# MiiChrono.net
KiCad netlist of a schematic drawn in EAGLE
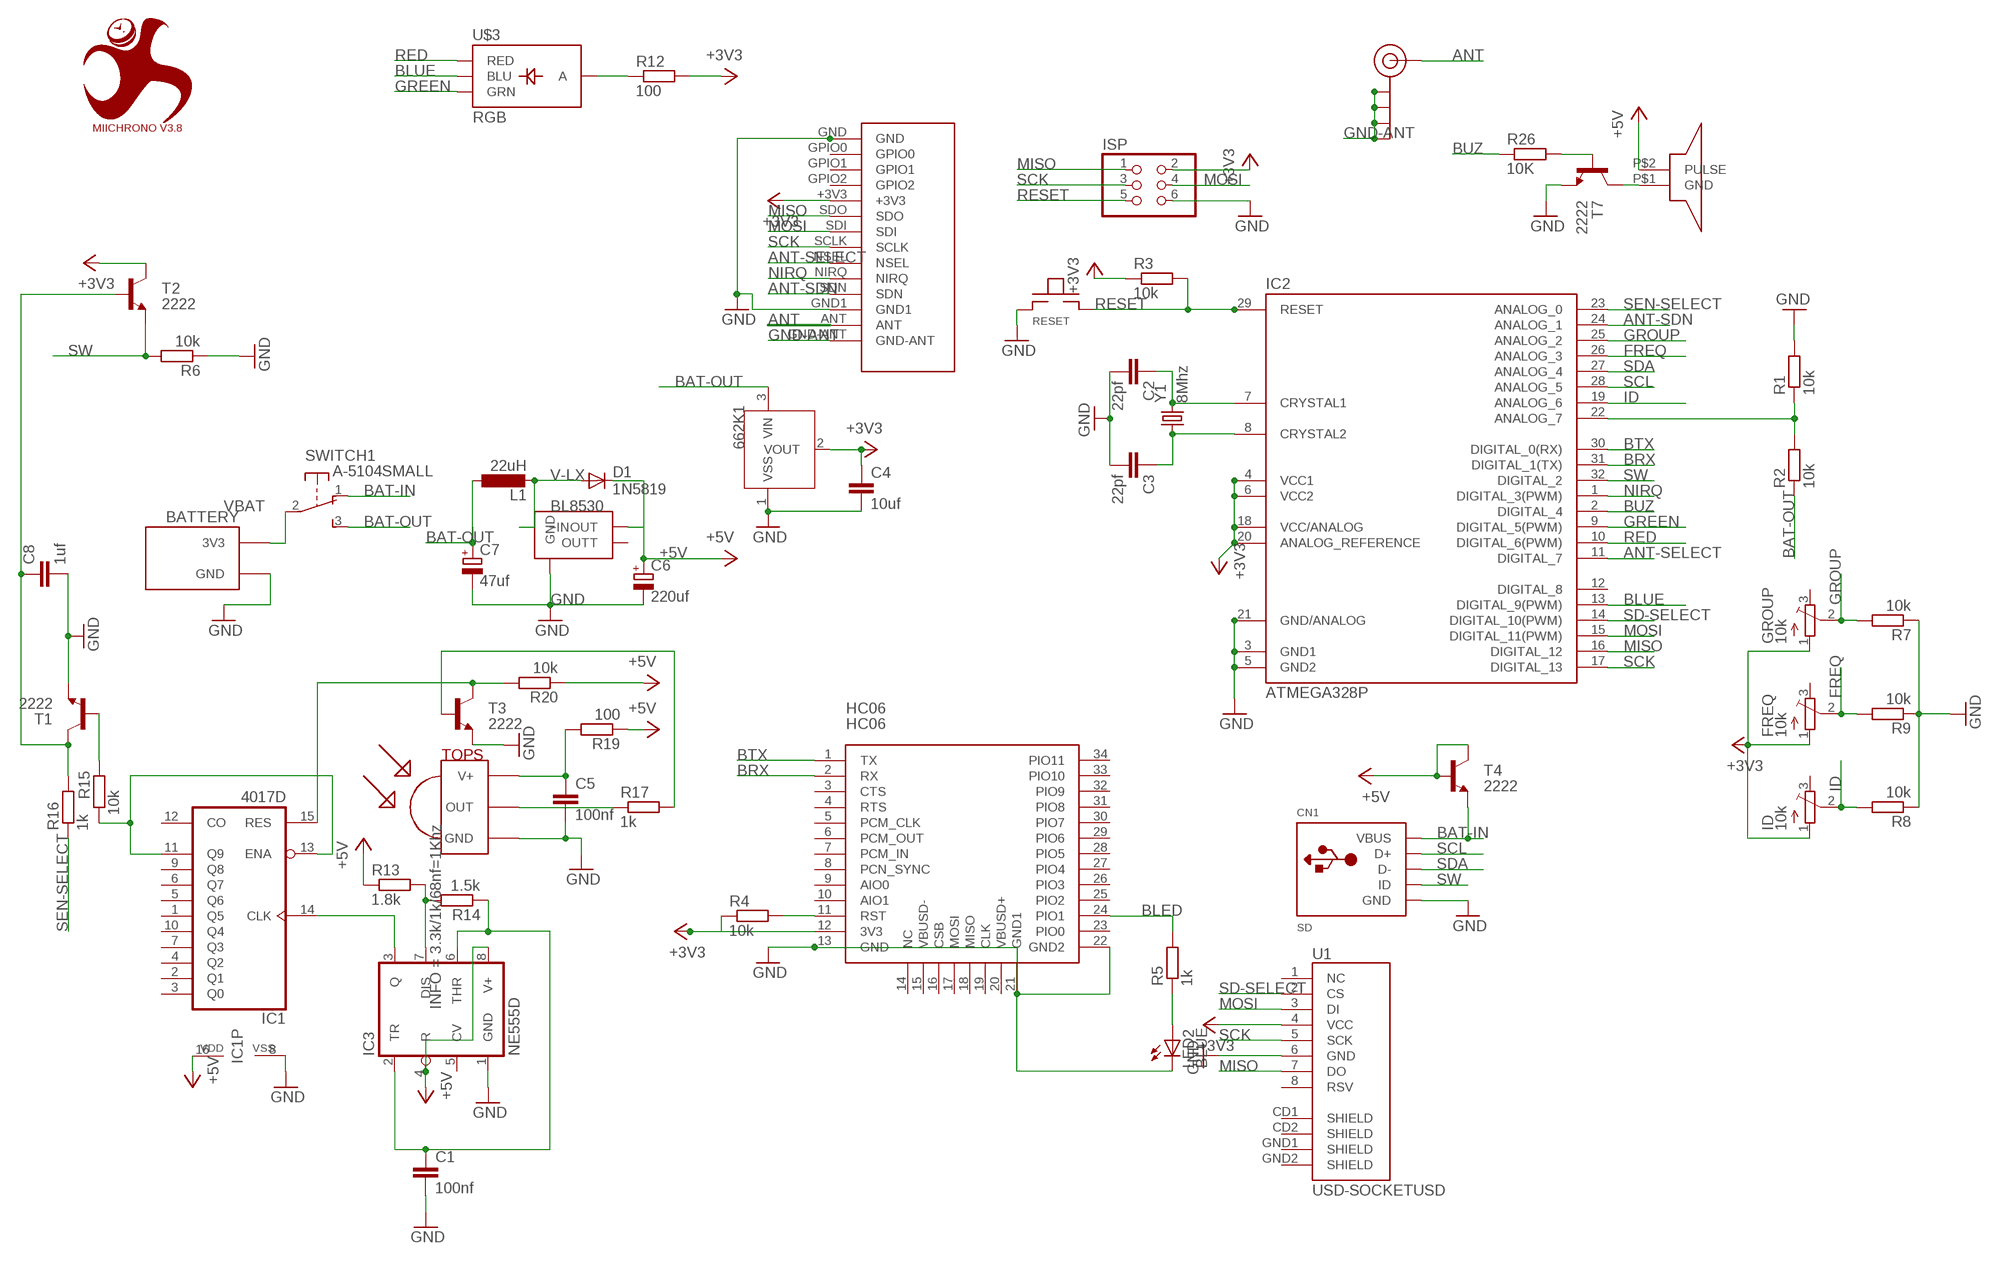
[diagram p0: schematic, sheet 1]

(export (version "E")
  (design (tool "Eeschema 10.0.6"))
  (components
    (comp (ref "662K1")
      (value "XC6206")
      (footprint "eagle-import:SOT23")
      (libsource (lib "eagle-import") (part "XC6206"))
    )
    (comp (ref "BATTERY")
      (value "GOPRO3BATTERY")
      (footprint "eagle-import:GOPRO3BATTERY")
      (libsource (lib "eagle-import") (part "GOPRO3BATTERY"))
    )
    (comp (ref "BL8530")
      (value "BL8530")
      (footprint "eagle-import:SOT89")
      (libsource (lib "eagle-import") (part "BL8530"))
    )
    (comp (ref "BUZZER")
      (value "BUZZER")
      (footprint "eagle-import:BUZZER")
      (libsource (lib "eagle-import") (part "BUZZER"))
    )
    (comp (ref "C1")
      (value "100nf")
      (footprint "eagle-import:C0805")
      (libsource (lib "eagle-import") (part "C-EUC0805"))
    )
    (comp (ref "C2")
      (value "22pf")
      (footprint "eagle-import:C0805")
      (libsource (lib "eagle-import") (part "C-EUC0805"))
    )
    (comp (ref "C3")
      (value "22pf")
      (footprint "eagle-import:C0805")
      (libsource (lib "eagle-import") (part "C-EUC0805"))
    )
    (comp (ref "C4")
      (value "10uf")
      (footprint "eagle-import:C0805")
      (libsource (lib "eagle-import") (part "C-EUC0805"))
    )
    (comp (ref "C5")
      (value "100nf")
      (footprint "eagle-import:C0805")
      (libsource (lib "eagle-import") (part "C-EUC0805"))
    )
    (comp (ref "C6")
      (value "220uf")
      (footprint "eagle-import:CT3528")
      (libsource (lib "eagle-import") (part "CPOL-EUCT3528"))
    )
    (comp (ref "C7")
      (value "47uf")
      (footprint "eagle-import:SMC_A")
      (libsource (lib "eagle-import") (part "CPOL-EUSMCA"))
    )
    (comp (ref "C8")
      (value "1uf")
      (footprint "eagle-import:C0805")
      (libsource (lib "eagle-import") (part "C-EUC0805"))
    )
    (comp (ref "CN1")
      (value "SD")
      (footprint "eagle-import:USB-MINIB")
      (libsource (lib "eagle-import") (part "USBMINIB"))
    )
    (comp (ref "D1")
      (value "1N5819")
      (footprint "eagle-import:DO214AC")
      (libsource (lib "eagle-import") (part "DIODE-DO214AC"))
    )
    (comp (ref "FREQ")
      (value "10k")
      (footprint "eagle-import:TC33X")
      (libsource (lib "eagle-import") (part "TRIMPOTTC33X"))
    )
    (comp (ref "GROUP")
      (value "10k")
      (footprint "eagle-import:TC33X")
      (libsource (lib "eagle-import") (part "TRIMPOTTC33X"))
    )
    (comp (ref "HC06")
      (value "HC06")
      (footprint "eagle-import:BLUETOOTH_SMD")
      (libsource (lib "eagle-import") (part "HC_05"))
    )
    (comp (ref "IC1")
      (value "4017D")
      (footprint "eagle-import:SO16")
      (libsource (lib "eagle-import") (part "4017D"))
    )
    (comp (ref "IC2")
      (value "ATMEGA328P")
      (footprint "eagle-import:TQFP32-08")
      (libsource (lib "eagle-import") (part "ATMEGA168-AU"))
    )
    (comp (ref "IC3")
      (value "NE555D")
      (footprint "eagle-import:SO08")
      (fields (field (name "INFO") "3.3k/1k/68nf=1Khz"))
      (libsource (lib "eagle-import") (part "555DNE"))
    )
    (comp (ref "ID")
      (value "10k")
      (footprint "eagle-import:TC33X")
      (libsource (lib "eagle-import") (part "TRIMPOTTC33X"))
    )
    (comp (ref "ISP")
      (value "PINHD-2X03_2.00")
      (footprint "eagle-import:2X03M")
      (libsource (lib "eagle-import") (part "PINHD-2X03_2.00"))
    )
    (comp (ref "J$1")
      (value "SMA_EDGE")
      (footprint "eagle-import:SMA-EDGE")
      (libsource (lib "eagle-import") (part "SMA_EDGE"))
    )
    (comp (ref "L1")
      (value "22uH")
      (footprint "eagle-import:L1812")
      (libsource (lib "eagle-import") (part "L-EUL1812"))
    )
    (comp (ref "LED2")
      (value "BLUE")
      (footprint "eagle-import:CHIP-LED0805")
      (libsource (lib "eagle-import") (part "LEDCHIP-LED0805"))
    )
    (comp (ref "R1")
      (value "10k")
      (footprint "eagle-import:R0805")
      (libsource (lib "eagle-import") (part "R-EU_R0805"))
    )
    (comp (ref "R2")
      (value "10k")
      (footprint "eagle-import:R0805")
      (libsource (lib "eagle-import") (part "R-EU_R0805"))
    )
    (comp (ref "R3")
      (value "10k")
      (footprint "eagle-import:R0805")
      (libsource (lib "eagle-import") (part "R-EU_R0805"))
    )
    (comp (ref "R4")
      (value "10k")
      (footprint "eagle-import:R0805")
      (libsource (lib "eagle-import") (part "R-EU_R0805"))
    )
    (comp (ref "R5")
      (value "1k")
      (footprint "eagle-import:R0805")
      (libsource (lib "eagle-import") (part "R-EU_R0805"))
    )
    (comp (ref "R6")
      (value "10k")
      (footprint "eagle-import:R0805")
      (libsource (lib "eagle-import") (part "R-EU_R0805"))
    )
    (comp (ref "R7")
      (value "10k")
      (footprint "eagle-import:R0805")
      (libsource (lib "eagle-import") (part "R-EU_R0805"))
    )
    (comp (ref "R8")
      (value "10k")
      (footprint "eagle-import:R0805")
      (libsource (lib "eagle-import") (part "R-EU_R0805"))
    )
    (comp (ref "R9")
      (value "10k")
      (footprint "eagle-import:R0805")
      (libsource (lib "eagle-import") (part "R-EU_R0805"))
    )
    (comp (ref "R12")
      (value "100")
      (footprint "eagle-import:R0805")
      (libsource (lib "eagle-import") (part "R-EU_R0805"))
    )
    (comp (ref "R13")
      (value "1.8k")
      (footprint "eagle-import:R0805")
      (libsource (lib "eagle-import") (part "R-EU_R0805"))
    )
    (comp (ref "R14")
      (value "1.5k")
      (footprint "eagle-import:R0805")
      (libsource (lib "eagle-import") (part "R-EU_R0805"))
    )
    (comp (ref "R15")
      (value "10k")
      (footprint "eagle-import:R0805")
      (libsource (lib "eagle-import") (part "R-EU_R0805"))
    )
    (comp (ref "R16")
      (value "1k")
      (footprint "eagle-import:R0805")
      (libsource (lib "eagle-import") (part "R-EU_R0805"))
    )
    (comp (ref "R17")
      (value "1k")
      (footprint "eagle-import:R0805")
      (libsource (lib "eagle-import") (part "R-EU_R0805"))
    )
    (comp (ref "R19")
      (value "100")
      (footprint "eagle-import:R0805")
      (libsource (lib "eagle-import") (part "R-EU_R0805"))
    )
    (comp (ref "R20")
      (value "10k")
      (footprint "eagle-import:R0805")
      (libsource (lib "eagle-import") (part "R-EU_R0805"))
    )
    (comp (ref "R26")
      (value "10K")
      (footprint "eagle-import:R0805")
      (libsource (lib "eagle-import") (part "R-EU_R0805"))
    )
    (comp (ref "RESET")
      (value "TACT")
      (footprint "eagle-import:TACT-TS-1289")
      (libsource (lib "eagle-import") (part "TACT"))
    )
    (comp (ref "SWITCH")
      (value "A-5104SMALL")
      (footprint "eagle-import:A-5104-SMALL")
      (libsource (lib "eagle-import") (part "A-5104SMALL"))
    )
    (comp (ref "T1")
      (value "2222")
      (footprint "eagle-import:SOT23")
      (libsource (lib "eagle-import") (part "TRANSISTOR_NPNSOT23"))
    )
    (comp (ref "T2")
      (value "2222")
      (footprint "eagle-import:SOT23")
      (libsource (lib "eagle-import") (part "TRANSISTOR_NPNSOT23"))
    )
    (comp (ref "T3")
      (value "2222")
      (footprint "eagle-import:SOT23")
      (libsource (lib "eagle-import") (part "TRANSISTOR_NPNSOT23"))
    )
    (comp (ref "T4")
      (value "2222")
      (footprint "eagle-import:SOT23")
      (libsource (lib "eagle-import") (part "TRANSISTOR_NPNSOT23"))
    )
    (comp (ref "T7")
      (value "2222")
      (footprint "eagle-import:SOT23")
      (libsource (lib "eagle-import") (part "TRANSISTOR_NPNSOT23"))
    )
    (comp (ref "TOPS")
      (value "TSOP4838")
      (footprint "eagle-import:TSOP18XX")
      (libsource (lib "eagle-import") (part "TSOP4838"))
    )
    (comp (ref "U$1")
      (value "MIICHRONO V3.8")
      (footprint "eagle-import:MIICHRONO")
      (libsource (lib "eagle-import") (part "MIICHRONO"))
    )
    (comp (ref "U$3")
      (value "RGB")
      (footprint "eagle-import:LED-TRICOLOR-SMD")
      (libsource (lib "eagle-import") (part "LED-TRICOLOR"))
    )
    (comp (ref "U$7")
      (value "SI4432")
      (footprint "eagle-import:SI4432")
      (libsource (lib "eagle-import") (part "SPI4432"))
    )
    (comp (ref "U1")
      (value "USD-SOCKETUSD")
      (footprint "eagle-import:USD-SOCKET-PP")
      (libsource (lib "eagle-import") (part "USD-SOCKETUSD"))
    )
    (comp (ref "Y1")
      (value "8Mhz")
      (footprint "eagle-import:HC49UP")
      (libsource (lib "eagle-import") (part "CRYSTALSMD"))
    )
  )
  (nets
    (net (code "1") (name "+3V3") (class "Default")
      (node (ref "662K1") (pin "2") (pinfunction "VOUT_2") (pintype "output"))
      (node (ref "C4") (pin "1") (pinfunction "1_1") (pintype "passive"))
      (node (ref "FREQ") (pin "1") (pinfunction "A_1") (pintype "passive"))
      (node (ref "GROUP") (pin "1") (pinfunction "A_1") (pintype "passive"))
      (node (ref "HC06") (pin "12") (pinfunction "3V3_12") (pintype "bidirectional"))
      (node (ref "IC2") (pin "18") (pinfunction "VCC/ANALOG_18") (pintype "passive"))
      (node (ref "IC2") (pin "20") (pinfunction "ANALOG_REFERENCE_20") (pintype "passive"))
      (node (ref "IC2") (pin "4") (pinfunction "VCC1_4") (pintype "power_in"))
      (node (ref "IC2") (pin "6") (pinfunction "VCC2_6") (pintype "power_in"))
      (node (ref "ID") (pin "1") (pinfunction "A_1") (pintype "passive"))
      (node (ref "ISP") (pin "2") (pinfunction "2_2") (pintype "passive"))
      (node (ref "R12") (pin "2") (pinfunction "2_2") (pintype "passive"))
      (node (ref "R3") (pin "1") (pinfunction "1_1") (pintype "passive"))
      (node (ref "R4") (pin "1") (pinfunction "1_1") (pintype "passive"))
      (node (ref "T2") (pin "3") (pinfunction "C_3") (pintype "passive"))
      (node (ref "U$7") (pin "+3V3") (pinfunction "+3V3_+3V3") (pintype "bidirectional"))
      (node (ref "U1") (pin "4") (pinfunction "VCC_4") (pintype "bidirectional"))
    )
    (net (code "2") (name "+5V") (class "Default")
      (node (ref "BL8530") (pin "2") (pinfunction "OUT_2") (pintype "bidirectional"))
      (node (ref "BUZZER") (pin "P$2") (pinfunction "PULSE_P$2") (pintype "bidirectional"))
      (node (ref "C6") (pin "+") (pinfunction "+_+") (pintype "passive"))
      (node (ref "D1") (pin "C") (pinfunction "C_C") (pintype "passive"))
      (node (ref "IC1") (pin "16") (pinfunction "VDD_16") (pintype "power_in"))
      (node (ref "IC3") (pin "4") (pinfunction "R_4") (pintype "input"))
      (node (ref "IC3") (pin "8") (pinfunction "V+_8") (pintype "power_in"))
      (node (ref "R13") (pin "1") (pinfunction "1_1") (pintype "passive"))
      (node (ref "R19") (pin "1") (pinfunction "1_1") (pintype "passive"))
      (node (ref "R20") (pin "1") (pinfunction "1_1") (pintype "passive"))
      (node (ref "T4") (pin "1") (pinfunction "B_1") (pintype "passive"))
      (node (ref "T4") (pin "3") (pinfunction "C_3") (pintype "passive"))
    )
    (net (code "3") (name "/ANT") (class "Default")
      (node (ref "J$1") (pin "SIG") (pinfunction "SIGNAL_SIG") (pintype "bidirectional"))
      (node (ref "U$7") (pin "ANT") (pinfunction "ANT_ANT") (pintype "bidirectional"))
    )
    (net (code "4") (name "/ANT-SDN") (class "Default")
      (node (ref "IC2") (pin "24") (pinfunction "ANALOG_1_24") (pintype "bidirectional"))
      (node (ref "U$7") (pin "SDN") (pinfunction "SDN_SDN") (pintype "bidirectional"))
    )
    (net (code "5") (name "/ANT-SELECT") (class "Default")
      (node (ref "IC2") (pin "11") (pinfunction "DIGITAL_7_11") (pintype "bidirectional"))
      (node (ref "U$7") (pin "NSEL") (pinfunction "NSEL_NSEL") (pintype "bidirectional"))
    )
    (net (code "6") (name "/BAT-IN") (class "Default")
      (node (ref "CN1") (pin "VBUS") (pinfunction "VBUS_VBUS") (pintype "power_in"))
      (node (ref "SWITCH") (pin "1") (pinfunction "O_1") (pintype "passive"))
      (node (ref "T4") (pin "2") (pinfunction "E_2") (pintype "passive"))
    )
    (net (code "7") (name "/BAT-OUT") (class "Default")
      (node (ref "662K1") (pin "3") (pinfunction "VIN_3") (pintype "input"))
      (node (ref "C7") (pin "+") (pinfunction "+_+") (pintype "passive"))
      (node (ref "L1") (pin "1") (pinfunction "1_1") (pintype "passive"))
      (node (ref "R2") (pin "1") (pinfunction "1_1") (pintype "passive"))
      (node (ref "SWITCH") (pin "3") (pinfunction "S_3") (pintype "passive"))
    )
    (net (code "8") (name "/BLED") (class "Default")
      (node (ref "HC06") (pin "24") (pinfunction "PIO1_24") (pintype "bidirectional"))
      (node (ref "R5") (pin "2") (pinfunction "2_2") (pintype "passive"))
    )
    (net (code "9") (name "/BLUE") (class "Default")
      (node (ref "IC2") (pin "13") (pinfunction "DIGITAL_9(PWM)_13") (pintype "bidirectional"))
      (node (ref "U$3") (pin "B") (pinfunction "BLU_B") (pintype "bidirectional"))
    )
    (net (code "10") (name "/BRX") (class "Default")
      (node (ref "HC06") (pin "2") (pinfunction "RX_2") (pintype "bidirectional"))
      (node (ref "IC2") (pin "31") (pinfunction "DIGITAL_1(TX)_31") (pintype "bidirectional"))
    )
    (net (code "11") (name "/BTX") (class "Default")
      (node (ref "HC06") (pin "1") (pinfunction "TX_1") (pintype "bidirectional"))
      (node (ref "IC2") (pin "30") (pinfunction "DIGITAL_0(RX)_30") (pintype "bidirectional"))
    )
    (net (code "12") (name "/BUZ") (class "Default")
      (node (ref "IC2") (pin "2") (pinfunction "DIGITAL_4_2") (pintype "bidirectional"))
      (node (ref "R26") (pin "1") (pinfunction "1_1") (pintype "passive"))
    )
    (net (code "13") (name "/FREQ") (class "Default")
      (node (ref "FREQ") (pin "2") (pinfunction "S_2") (pintype "passive"))
      (node (ref "IC2") (pin "26") (pinfunction "ANALOG_3_26") (pintype "bidirectional"))
      (node (ref "R9") (pin "2") (pinfunction "2_2") (pintype "passive"))
    )
    (net (code "14") (name "/GND-ANT") (class "Default")
      (node (ref "J$1") (pin "GND@0") (pinfunction "GND_GND@0") (pintype "bidirectional"))
      (node (ref "J$1") (pin "GND@1") (pinfunction "GND_GND@1") (pintype "bidirectional"))
      (node (ref "J$1") (pin "GND@2") (pinfunction "GND_GND@2") (pintype "bidirectional"))
      (node (ref "J$1") (pin "GND@3") (pinfunction "GND_GND@3") (pintype "bidirectional"))
      (node (ref "U$7") (pin "GND-ANT") (pinfunction "GND-ANT_GND-ANT") (pintype "bidirectional"))
    )
    (net (code "15") (name "/GREEN") (class "Default")
      (node (ref "IC2") (pin "9") (pinfunction "DIGITAL_5(PWM)_9") (pintype "bidirectional"))
      (node (ref "U$3") (pin "G") (pinfunction "GRN_G") (pintype "bidirectional"))
    )
    (net (code "16") (name "/GROUP") (class "Default")
      (node (ref "GROUP") (pin "2") (pinfunction "S_2") (pintype "passive"))
      (node (ref "IC2") (pin "25") (pinfunction "ANALOG_2_25") (pintype "bidirectional"))
      (node (ref "R7") (pin "2") (pinfunction "2_2") (pintype "passive"))
    )
    (net (code "17") (name "/ID") (class "Default")
      (node (ref "IC2") (pin "19") (pinfunction "ANALOG_6_19") (pintype "passive"))
      (node (ref "ID") (pin "2") (pinfunction "S_2") (pintype "passive"))
      (node (ref "R8") (pin "2") (pinfunction "2_2") (pintype "passive"))
    )
    (net (code "18") (name "/MISO") (class "Default")
      (node (ref "IC2") (pin "16") (pinfunction "DIGITAL_12_16") (pintype "bidirectional"))
      (node (ref "ISP") (pin "1") (pinfunction "1_1") (pintype "passive"))
      (node (ref "U$7") (pin "SDO") (pinfunction "SDO_SDO") (pintype "bidirectional"))
      (node (ref "U1") (pin "7") (pinfunction "DO_7") (pintype "bidirectional"))
    )
    (net (code "19") (name "/MOSI") (class "Default")
      (node (ref "IC2") (pin "15") (pinfunction "DIGITAL_11(PWM)_15") (pintype "bidirectional"))
      (node (ref "ISP") (pin "4") (pinfunction "4_4") (pintype "passive"))
      (node (ref "U$7") (pin "SDI") (pinfunction "SDI_SDI") (pintype "bidirectional"))
      (node (ref "U1") (pin "3") (pinfunction "DI_3") (pintype "bidirectional"))
    )
    (net (code "20") (name "/NIRQ") (class "Default")
      (node (ref "IC2") (pin "1") (pinfunction "DIGITAL_3(PWM)_1") (pintype "bidirectional"))
      (node (ref "U$7") (pin "NIRQ") (pinfunction "NIRQ_NIRQ") (pintype "bidirectional"))
    )
    (net (code "21") (name "/RED") (class "Default")
      (node (ref "IC2") (pin "10") (pinfunction "DIGITAL_6(PWM)_10") (pintype "bidirectional"))
      (node (ref "U$3") (pin "R") (pinfunction "RED_R") (pintype "bidirectional"))
    )
    (net (code "22") (name "/RESET") (class "Default")
      (node (ref "IC2") (pin "29") (pinfunction "RESET_29") (pintype "bidirectional"))
      (node (ref "ISP") (pin "5") (pinfunction "5_5") (pintype "passive"))
      (node (ref "R3") (pin "2") (pinfunction "2_2") (pintype "passive"))
      (node (ref "RESET") (pin "BOT-2") (pinfunction "P$2_BOT-2") (pintype "bidirectional"))
    )
    (net (code "23") (name "/SCK") (class "Default")
      (node (ref "IC2") (pin "17") (pinfunction "DIGITAL_13_17") (pintype "bidirectional"))
      (node (ref "ISP") (pin "3") (pinfunction "3_3") (pintype "passive"))
      (node (ref "U$7") (pin "SCLK") (pinfunction "SCLK_SCLK") (pintype "bidirectional"))
      (node (ref "U1") (pin "5") (pinfunction "SCK_5") (pintype "bidirectional"))
    )
    (net (code "24") (name "/SCL") (class "Default")
      (node (ref "CN1") (pin "D+") (pinfunction "D+_D+") (pintype "bidirectional"))
      (node (ref "IC2") (pin "28") (pinfunction "ANALOG_5_28") (pintype "bidirectional"))
    )
    (net (code "25") (name "/SD-SELECT") (class "Default")
      (node (ref "IC2") (pin "14") (pinfunction "DIGITAL_10(PWM)_14") (pintype "bidirectional"))
      (node (ref "U1") (pin "2") (pinfunction "CS_2") (pintype "bidirectional"))
    )
    (net (code "26") (name "/SDA") (class "Default")
      (node (ref "CN1") (pin "D-") (pinfunction "D-_D-") (pintype "bidirectional"))
      (node (ref "IC2") (pin "27") (pinfunction "ANALOG_4_27") (pintype "bidirectional"))
    )
    (net (code "27") (name "/SEN-SELECT") (class "Default")
      (node (ref "IC2") (pin "23") (pinfunction "ANALOG_0_23") (pintype "bidirectional"))
      (node (ref "R16") (pin "1") (pinfunction "1_1") (pintype "passive"))
    )
    (net (code "28") (name "/SW") (class "Default")
      (node (ref "CN1") (pin "ID") (pinfunction "ID_ID") (pintype "bidirectional"))
      (node (ref "IC2") (pin "32") (pinfunction "DIGITAL_2_32") (pintype "bidirectional"))
      (node (ref "R6") (pin "2") (pinfunction "2_2") (pintype "passive"))
      (node (ref "T2") (pin "2") (pinfunction "E_2") (pintype "passive"))
    )
    (net (code "29") (name "/V-LX") (class "Default")
      (node (ref "BL8530") (pin "3") (pinfunction "~{IN}_3") (pintype "bidirectional"))
      (node (ref "D1") (pin "A") (pinfunction "A_A") (pintype "passive"))
      (node (ref "L1") (pin "2") (pinfunction "2_2") (pintype "passive"))
    )
    (net (code "30") (name "/VBAT") (class "Default")
      (node (ref "BATTERY") (pin "3V3") (pinfunction "3V3_3V3") (pintype "bidirectional"))
      (node (ref "SWITCH") (pin "2") (pinfunction "P_2") (pintype "passive"))
    )
    (net (code "31") (name "GND") (class "Default")
      (node (ref "662K1") (pin "1") (pinfunction "VSS_1") (pintype "power_in"))
      (node (ref "BATTERY") (pin "GND") (pinfunction "GND_GND") (pintype "bidirectional"))
      (node (ref "BL8530") (pin "1") (pinfunction "GND_1") (pintype "bidirectional"))
      (node (ref "C1") (pin "2") (pinfunction "2_2") (pintype "passive"))
      (node (ref "C2") (pin "2") (pinfunction "2_2") (pintype "passive"))
      (node (ref "C3") (pin "2") (pinfunction "2_2") (pintype "passive"))
      (node (ref "C4") (pin "2") (pinfunction "2_2") (pintype "passive"))
      (node (ref "C5") (pin "2") (pinfunction "2_2") (pintype "passive"))
      (node (ref "C6") (pin "-") (pinfunction "-_-") (pintype "passive"))
      (node (ref "C7") (pin "-") (pinfunction "-_-") (pintype "passive"))
      (node (ref "C8") (pin "2") (pinfunction "2_2") (pintype "passive"))
      (node (ref "CN1") (pin "GND") (pinfunction "GND_GND") (pintype "power_in"))
      (node (ref "HC06") (pin "13") (pinfunction "GND_13") (pintype "bidirectional"))
      (node (ref "HC06") (pin "21") (pinfunction "GND1_21") (pintype "bidirectional"))
      (node (ref "HC06") (pin "22") (pinfunction "GND2_22") (pintype "bidirectional"))
      (node (ref "IC1") (pin "8") (pinfunction "VSS_8") (pintype "power_in"))
      (node (ref "IC2") (pin "21") (pinfunction "GND/ANALOG_21") (pintype "power_in"))
      (node (ref "IC2") (pin "3") (pinfunction "GND1_3") (pintype "power_in"))
      (node (ref "IC2") (pin "5") (pinfunction "GND2_5") (pintype "power_in"))
      (node (ref "IC3") (pin "1") (pinfunction "GND_1") (pintype "power_in"))
      (node (ref "ISP") (pin "6") (pinfunction "6_6") (pintype "passive"))
      (node (ref "LED2") (pin "C") (pinfunction "C_C") (pintype "passive"))
      (node (ref "R1") (pin "2") (pinfunction "2_2") (pintype "passive"))
      (node (ref "R6") (pin "1") (pinfunction "1_1") (pintype "passive"))
      (node (ref "R7") (pin "1") (pinfunction "1_1") (pintype "passive"))
      (node (ref "R8") (pin "1") (pinfunction "1_1") (pintype "passive"))
      (node (ref "R9") (pin "1") (pinfunction "1_1") (pintype "passive"))
      (node (ref "RESET") (pin "TOP-1") (pinfunction "P$1_TOP-1") (pintype "bidirectional"))
      (node (ref "T1") (pin "2") (pinfunction "E_2") (pintype "passive"))
      (node (ref "T3") (pin "2") (pinfunction "E_2") (pintype "passive"))
      (node (ref "T7") (pin "2") (pinfunction "E_2") (pintype "passive"))
      (node (ref "TOPS") (pin "GND") (pinfunction "GND_GND") (pintype "bidirectional"))
      (node (ref "U$7") (pin "GND") (pinfunction "GND_GND") (pintype "bidirectional"))
      (node (ref "U$7") (pin "GND1") (pinfunction "GND1_GND1") (pintype "bidirectional"))
      (node (ref "U1") (pin "6") (pinfunction "GND_6") (pintype "bidirectional"))
    )
    (net (code "32") (name "Net-(BUZZER-GND)") (class "Default")
      (node (ref "BUZZER") (pin "P$1") (pinfunction "GND_P$1") (pintype "bidirectional"))
      (node (ref "T7") (pin "3") (pinfunction "C_3") (pintype "passive"))
    )
    (net (code "33") (name "Net-(HC06-RST)") (class "Default")
      (node (ref "HC06") (pin "11") (pinfunction "RST_11") (pintype "bidirectional"))
      (node (ref "R4") (pin "2") (pinfunction "2_2") (pintype "passive"))
    )
    (net (code "34") (name "Net-(IC1A-CLK)") (class "Default")
      (node (ref "IC1") (pin "14") (pinfunction "CLK_14") (pintype "input"))
      (node (ref "IC3") (pin "3") (pinfunction "Q_3") (pintype "output"))
    )
    (net (code "35") (name "Net-(IC1A-ENA)") (class "Default")
      (node (ref "IC1") (pin "11") (pinfunction "Q9_11") (pintype "output"))
      (node (ref "IC1") (pin "13") (pinfunction "ENA_13") (pintype "input"))
      (node (ref "R15") (pin "1") (pinfunction "1_1") (pintype "passive"))
    )
    (net (code "36") (name "Net-(IC1A-RES)") (class "Default")
      (node (ref "IC1") (pin "15") (pinfunction "RES_15") (pintype "input"))
      (node (ref "R20") (pin "2") (pinfunction "2_2") (pintype "passive"))
      (node (ref "T3") (pin "3") (pinfunction "C_3") (pintype "passive"))
    )
    (net (code "37") (name "Net-(IC2-ANALOG_7)") (class "Default")
      (node (ref "IC2") (pin "22") (pinfunction "ANALOG_7_22") (pintype "passive"))
      (node (ref "R1") (pin "1") (pinfunction "1_1") (pintype "passive"))
      (node (ref "R2") (pin "2") (pinfunction "2_2") (pintype "passive"))
    )
    (net (code "38") (name "Net-(IC2-CRYSTAL1)") (class "Default")
      (node (ref "C2") (pin "1") (pinfunction "1_1") (pintype "passive"))
      (node (ref "IC2") (pin "7") (pinfunction "CRYSTAL1_7") (pintype "bidirectional"))
      (node (ref "Y1") (pin "2") (pinfunction "2_2") (pintype "passive"))
    )
    (net (code "39") (name "Net-(IC2-CRYSTAL2)") (class "Default")
      (node (ref "C3") (pin "1") (pinfunction "1_1") (pintype "passive"))
      (node (ref "IC2") (pin "8") (pinfunction "CRYSTAL2_8") (pintype "bidirectional"))
      (node (ref "Y1") (pin "1") (pinfunction "1_1") (pintype "passive"))
    )
    (net (code "40") (name "Net-(IC3-DIS)") (class "Default")
      (node (ref "IC3") (pin "7") (pinfunction "DIS_7") (pintype "input"))
      (node (ref "R13") (pin "2") (pinfunction "2_2") (pintype "passive"))
      (node (ref "R14") (pin "2") (pinfunction "2_2") (pintype "passive"))
    )
    (net (code "41") (name "Net-(IC3-THR)") (class "Default")
      (node (ref "C1") (pin "1") (pinfunction "1_1") (pintype "passive"))
      (node (ref "IC3") (pin "2") (pinfunction "TR_2") (pintype "input"))
      (node (ref "IC3") (pin "6") (pinfunction "THR_6") (pintype "input"))
      (node (ref "R14") (pin "1") (pinfunction "1_1") (pintype "passive"))
    )
    (net (code "42") (name "Net-(LED2-PadA)") (class "Default")
      (node (ref "LED2") (pin "A") (pinfunction "A_A") (pintype "passive"))
      (node (ref "R5") (pin "1") (pinfunction "1_1") (pintype "passive"))
    )
    (net (code "43") (name "Net-(R12-Pad1)") (class "Default")
      (node (ref "R12") (pin "1") (pinfunction "1_1") (pintype "passive"))
      (node (ref "U$3") (pin "A") (pinfunction "A_A") (pintype "bidirectional"))
    )
    (net (code "44") (name "Net-(R17-Pad1)") (class "Default")
      (node (ref "R17") (pin "1") (pinfunction "1_1") (pintype "passive"))
      (node (ref "TOPS") (pin "OUT") (pinfunction "OUT_OUT") (pintype "bidirectional"))
    )
    (net (code "45") (name "Net-(T1-B)") (class "Default")
      (node (ref "R15") (pin "2") (pinfunction "2_2") (pintype "passive"))
      (node (ref "T1") (pin "1") (pinfunction "B_1") (pintype "passive"))
    )
    (net (code "46") (name "Net-(T1-C)") (class "Default")
      (node (ref "C8") (pin "1") (pinfunction "1_1") (pintype "passive"))
      (node (ref "R16") (pin "2") (pinfunction "2_2") (pintype "passive"))
      (node (ref "T1") (pin "3") (pinfunction "C_3") (pintype "passive"))
      (node (ref "T2") (pin "1") (pinfunction "B_1") (pintype "passive"))
    )
    (net (code "47") (name "Net-(T3-B)") (class "Default")
      (node (ref "R17") (pin "2") (pinfunction "2_2") (pintype "passive"))
      (node (ref "T3") (pin "1") (pinfunction "B_1") (pintype "passive"))
    )
    (net (code "48") (name "Net-(T7-B)") (class "Default")
      (node (ref "R26") (pin "2") (pinfunction "2_2") (pintype "passive"))
      (node (ref "T7") (pin "1") (pinfunction "B_1") (pintype "passive"))
    )
    (net (code "49") (name "Net-(TOPS-V+)") (class "Default")
      (node (ref "C5") (pin "1") (pinfunction "1_1") (pintype "passive"))
      (node (ref "R19") (pin "2") (pinfunction "2_2") (pintype "passive"))
      (node (ref "TOPS") (pin "VCC") (pinfunction "V+_VCC") (pintype "bidirectional"))
    )
    (net (code "50") (name "unconnected-(BL8530-OUTT-Pad4)") (class "Default")
      (node (ref "BL8530") (pin "4") (pinfunction "OUTT_4") (pintype "bidirectional"))
    )
    (net (code "51") (name "unconnected-(FREQ-E-Pad3)") (class "Default")
      (node (ref "FREQ") (pin "3") (pinfunction "E_3") (pintype "passive"))
    )
    (net (code "52") (name "unconnected-(GROUP-E-Pad3)") (class "Default")
      (node (ref "GROUP") (pin "3") (pinfunction "E_3") (pintype "passive"))
    )
    (net (code "53") (name "unconnected-(HC06-AIO0-Pad9)") (class "Default")
      (node (ref "HC06") (pin "9") (pinfunction "AIO0_9") (pintype "bidirectional"))
    )
    (net (code "54") (name "unconnected-(HC06-AIO1-Pad10)") (class "Default")
      (node (ref "HC06") (pin "10") (pinfunction "AIO1_10") (pintype "bidirectional"))
    )
    (net (code "55") (name "unconnected-(HC06-CLK-Pad19)") (class "Default")
      (node (ref "HC06") (pin "19") (pinfunction "CLK_19") (pintype "bidirectional"))
    )
    (net (code "56") (name "unconnected-(HC06-CSB-Pad16)") (class "Default")
      (node (ref "HC06") (pin "16") (pinfunction "CSB_16") (pintype "bidirectional"))
    )
    (net (code "57") (name "unconnected-(HC06-CTS-Pad3)") (class "Default")
      (node (ref "HC06") (pin "3") (pinfunction "CTS_3") (pintype "bidirectional"))
    )
    (net (code "58") (name "unconnected-(HC06-MISO-Pad18)") (class "Default")
      (node (ref "HC06") (pin "18") (pinfunction "MISO_18") (pintype "bidirectional"))
    )
    (net (code "59") (name "unconnected-(HC06-MOSI-Pad17)") (class "Default")
      (node (ref "HC06") (pin "17") (pinfunction "MOSI_17") (pintype "bidirectional"))
    )
    (net (code "60") (name "unconnected-(HC06-NC-Pad14)") (class "Default")
      (node (ref "HC06") (pin "14") (pinfunction "NC_14") (pintype "bidirectional"))
    )
    (net (code "61") (name "unconnected-(HC06-PCM_CLK-Pad5)") (class "Default")
      (node (ref "HC06") (pin "5") (pinfunction "PCM_CLK_5") (pintype "bidirectional"))
    )
    (net (code "62") (name "unconnected-(HC06-PCM_IN-Pad7)") (class "Default")
      (node (ref "HC06") (pin "7") (pinfunction "PCM_IN_7") (pintype "bidirectional"))
    )
    (net (code "63") (name "unconnected-(HC06-PCM_OUT-Pad6)") (class "Default")
      (node (ref "HC06") (pin "6") (pinfunction "PCM_OUT_6") (pintype "bidirectional"))
    )
    (net (code "64") (name "unconnected-(HC06-PCN_SYNC-Pad8)") (class "Default")
      (node (ref "HC06") (pin "8") (pinfunction "PCN_SYNC_8") (pintype "bidirectional"))
    )
    (net (code "65") (name "unconnected-(HC06-PIO0-Pad23)") (class "Default")
      (node (ref "HC06") (pin "23") (pinfunction "PIO0_23") (pintype "bidirectional"))
    )
    (net (code "66") (name "unconnected-(HC06-PIO2-Pad25)") (class "Default")
      (node (ref "HC06") (pin "25") (pinfunction "PIO2_25") (pintype "bidirectional"))
    )
    (net (code "67") (name "unconnected-(HC06-PIO3-Pad26)") (class "Default")
      (node (ref "HC06") (pin "26") (pinfunction "PIO3_26") (pintype "bidirectional"))
    )
    (net (code "68") (name "unconnected-(HC06-PIO4-Pad27)") (class "Default")
      (node (ref "HC06") (pin "27") (pinfunction "PIO4_27") (pintype "bidirectional"))
    )
    (net (code "69") (name "unconnected-(HC06-PIO5-Pad28)") (class "Default")
      (node (ref "HC06") (pin "28") (pinfunction "PIO5_28") (pintype "bidirectional"))
    )
    (net (code "70") (name "unconnected-(HC06-PIO6-Pad29)") (class "Default")
      (node (ref "HC06") (pin "29") (pinfunction "PIO6_29") (pintype "bidirectional"))
    )
    (net (code "71") (name "unconnected-(HC06-PIO7-Pad30)") (class "Default")
      (node (ref "HC06") (pin "30") (pinfunction "PIO7_30") (pintype "bidirectional"))
    )
    (net (code "72") (name "unconnected-(HC06-PIO8-Pad31)") (class "Default")
      (node (ref "HC06") (pin "31") (pinfunction "PIO8_31") (pintype "bidirectional"))
    )
    (net (code "73") (name "unconnected-(HC06-PIO9-Pad32)") (class "Default")
      (node (ref "HC06") (pin "32") (pinfunction "PIO9_32") (pintype "bidirectional"))
    )
    (net (code "74") (name "unconnected-(HC06-PIO10-Pad33)") (class "Default")
      (node (ref "HC06") (pin "33") (pinfunction "PIO10_33") (pintype "bidirectional"))
    )
    (net (code "75") (name "unconnected-(HC06-PIO11-Pad34)") (class "Default")
      (node (ref "HC06") (pin "34") (pinfunction "PIO11_34") (pintype "bidirectional"))
    )
    (net (code "76") (name "unconnected-(HC06-RTS-Pad4)") (class "Default")
      (node (ref "HC06") (pin "4") (pinfunction "RTS_4") (pintype "bidirectional"))
    )
    (net (code "77") (name "unconnected-(HC06-VBUSD+-Pad20)") (class "Default")
      (node (ref "HC06") (pin "20") (pinfunction "VBUSD+_20") (pintype "bidirectional"))
    )
    (net (code "78") (name "unconnected-(HC06-VBUSD--Pad15)") (class "Default")
      (node (ref "HC06") (pin "15") (pinfunction "VBUSD-_15") (pintype "bidirectional"))
    )
    (net (code "79") (name "unconnected-(IC1A-CO-Pad12)") (class "Default")
      (node (ref "IC1") (pin "12") (pinfunction "CO_12") (pintype "output"))
    )
    (net (code "80") (name "unconnected-(IC1A-Q0-Pad3)") (class "Default")
      (node (ref "IC1") (pin "3") (pinfunction "Q0_3") (pintype "output"))
    )
    (net (code "81") (name "unconnected-(IC1A-Q1-Pad2)") (class "Default")
      (node (ref "IC1") (pin "2") (pinfunction "Q1_2") (pintype "output"))
    )
    (net (code "82") (name "unconnected-(IC1A-Q2-Pad4)") (class "Default")
      (node (ref "IC1") (pin "4") (pinfunction "Q2_4") (pintype "output"))
    )
    (net (code "83") (name "unconnected-(IC1A-Q3-Pad7)") (class "Default")
      (node (ref "IC1") (pin "7") (pinfunction "Q3_7") (pintype "output"))
    )
    (net (code "84") (name "unconnected-(IC1A-Q4-Pad10)") (class "Default")
      (node (ref "IC1") (pin "10") (pinfunction "Q4_10") (pintype "output"))
    )
    (net (code "85") (name "unconnected-(IC1A-Q5-Pad1)") (class "Default")
      (node (ref "IC1") (pin "1") (pinfunction "Q5_1") (pintype "output"))
    )
    (net (code "86") (name "unconnected-(IC1A-Q6-Pad5)") (class "Default")
      (node (ref "IC1") (pin "5") (pinfunction "Q6_5") (pintype "output"))
    )
    (net (code "87") (name "unconnected-(IC1A-Q7-Pad6)") (class "Default")
      (node (ref "IC1") (pin "6") (pinfunction "Q7_6") (pintype "output"))
    )
    (net (code "88") (name "unconnected-(IC1A-Q8-Pad9)") (class "Default")
      (node (ref "IC1") (pin "9") (pinfunction "Q8_9") (pintype "output"))
    )
    (net (code "89") (name "unconnected-(IC2-DIGITAL_8-Pad12)") (class "Default")
      (node (ref "IC2") (pin "12") (pinfunction "DIGITAL_8_12") (pintype "bidirectional"))
    )
    (net (code "90") (name "unconnected-(IC3-CV-Pad5)") (class "Default")
      (node (ref "IC3") (pin "5") (pinfunction "CV_5") (pintype "input"))
    )
    (net (code "91") (name "unconnected-(ID-E-Pad3)") (class "Default")
      (node (ref "ID") (pin "3") (pinfunction "E_3") (pintype "passive"))
    )
    (net (code "92") (name "unconnected-(U$7-PadGPIO0)") (class "Default")
      (node (ref "U$7") (pin "GPIO0") (pinfunction "GPIO0_GPIO0") (pintype "bidirectional"))
    )
    (net (code "93") (name "unconnected-(U$7-PadGPIO1)") (class "Default")
      (node (ref "U$7") (pin "GPIO1") (pinfunction "GPIO1_GPIO1") (pintype "bidirectional"))
    )
    (net (code "94") (name "unconnected-(U$7-PadGPIO2)") (class "Default")
      (node (ref "U$7") (pin "GPIO2") (pinfunction "GPIO2_GPIO2") (pintype "bidirectional"))
    )
    (net (code "95") (name "unconnected-(U1-NC-Pad1)") (class "Default")
      (node (ref "U1") (pin "1") (pinfunction "NC_1") (pintype "bidirectional"))
    )
    (net (code "96") (name "unconnected-(U1-RSV-Pad8)") (class "Default")
      (node (ref "U1") (pin "8") (pinfunction "RSV_8") (pintype "bidirectional"))
    )
    (net (code "97") (name "unconnected-(U1-SHIELD-PadCD1)") (class "Default")
      (node (ref "U1") (pin "CD1") (pinfunction "SHIELD_CD1") (pintype "bidirectional"))
    )
    (net (code "98") (name "unconnected-(U1-SHIELD-PadCD2)") (class "Default")
      (node (ref "U1") (pin "CD2") (pinfunction "SHIELD_CD2") (pintype "bidirectional"))
    )
    (net (code "99") (name "unconnected-(U1-SHIELD-PadGND1)") (class "Default")
      (node (ref "U1") (pin "GND1") (pinfunction "SHIELD_GND1") (pintype "bidirectional"))
    )
    (net (code "100") (name "unconnected-(U1-SHIELD-PadGND2)") (class "Default")
      (node (ref "U1") (pin "GND2") (pinfunction "SHIELD_GND2") (pintype "bidirectional"))
    )
  )
)
